# schematic.net
KiCad netlist of a schematic drawn in EAGLE
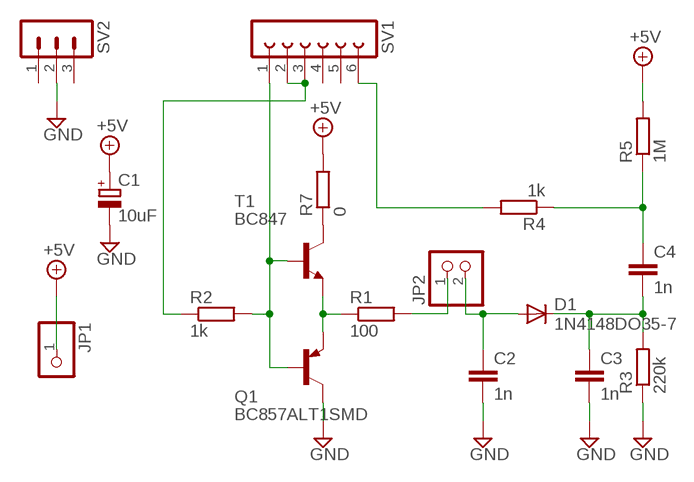
[diagram p0: schematic, sheet 1]

(export (version "E")
  (design (tool "Eeschema 10.0.6"))
  (components
    (comp (ref "C1")
      (value "10uF")
      (footprint "eagle-import:E2,5-6")
      (libsource (lib "eagle-import") (part "CPOL-EUE2.5-6"))
    )
    (comp (ref "C2")
      (value "1n")
      (footprint "eagle-import:C050-024X044")
      (libsource (lib "eagle-import") (part "C-EU050-024X044"))
    )
    (comp (ref "C3")
      (value "1n")
      (footprint "eagle-import:C050-024X044")
      (libsource (lib "eagle-import") (part "C-EU050-024X044"))
    )
    (comp (ref "C4")
      (value "1n")
      (footprint "eagle-import:C050-024X044")
      (libsource (lib "eagle-import") (part "C-EU050-024X044"))
    )
    (comp (ref "D1")
      (value "1N4148DO35-7")
      (footprint "eagle-import:DO35-7")
      (libsource (lib "eagle-import") (part "1N4148DO35-7"))
    )
    (comp (ref "JP1")
      (value "PINHD-1X1")
      (footprint "eagle-import:1X01")
      (libsource (lib "eagle-import") (part "PINHD-1X1"))
    )
    (comp (ref "JP2")
      (value "PINHD-1X2")
      (footprint "eagle-import:1X02")
      (libsource (lib "eagle-import") (part "PINHD-1X2"))
    )
    (comp (ref "Q1")
      (value "BC857ALT1SMD")
      (footprint "eagle-import:SOT23-BEC")
      (libsource (lib "eagle-import") (part "BC857SMDALT1"))
    )
    (comp (ref "R1")
      (value "100")
      (footprint "eagle-import:0207_10")
      (libsource (lib "eagle-import") (part "R-EU_0207/10"))
    )
    (comp (ref "R2")
      (value "1k")
      (footprint "eagle-import:0207_10")
      (libsource (lib "eagle-import") (part "R-EU_0207/10"))
    )
    (comp (ref "R3")
      (value "220k")
      (footprint "eagle-import:0207_10")
      (libsource (lib "eagle-import") (part "R-EU_0207/10"))
    )
    (comp (ref "R4")
      (value "1k")
      (footprint "eagle-import:0207_10")
      (libsource (lib "eagle-import") (part "R-EU_0207/10"))
    )
    (comp (ref "R5")
      (value "1M")
      (footprint "eagle-import:0207_10")
      (libsource (lib "eagle-import") (part "R-EU_0207/10"))
    )
    (comp (ref "R7")
      (value "0")
      (footprint "eagle-import:0204_5")
      (libsource (lib "eagle-import") (part "R-EU_0204/5"))
    )
    (comp (ref "SV1")
      (value "FE06-1")
      (footprint "eagle-import:FE06")
      (libsource (lib "eagle-import") (part "FE06-1"))
    )
    (comp (ref "SV2")
      (value "MA03-1")
      (footprint "eagle-import:MA03-1")
      (libsource (lib "eagle-import") (part "MA03-1"))
    )
    (comp (ref "T1")
      (value "BC847")
      (footprint "eagle-import:SOT23")
      (libsource (lib "eagle-import") (part "BC847"))
    )
  )
  (nets
    (net (code "1") (name "+5V") (class "Default")
      (node (ref "C1") (pin "+") (pinfunction "+_+") (pintype "passive"))
      (node (ref "JP1") (pin "1") (pinfunction "1_1") (pintype "passive"))
      (node (ref "R5") (pin "2") (pinfunction "2_2") (pintype "passive"))
      (node (ref "R7") (pin "2") (pinfunction "2_2") (pintype "passive"))
    )
    (net (code "2") (name "GND") (class "Default")
      (node (ref "C1") (pin "-") (pinfunction "-_-") (pintype "passive"))
      (node (ref "C2") (pin "2") (pinfunction "2_2") (pintype "passive"))
      (node (ref "C3") (pin "2") (pinfunction "2_2") (pintype "passive"))
      (node (ref "Q1") (pin "C") (pinfunction "C_C") (pintype "passive"))
      (node (ref "R3") (pin "1") (pinfunction "1_1") (pintype "passive"))
      (node (ref "SV2") (pin "2") (pinfunction "2_2") (pintype "passive"))
    )
    (net (code "3") (name "Net-(C2-Pad1)") (class "Default")
      (node (ref "C2") (pin "1") (pinfunction "1_1") (pintype "passive"))
      (node (ref "D1") (pin "A") (pinfunction "A_A") (pintype "passive"))
      (node (ref "JP2") (pin "2") (pinfunction "2_2") (pintype "passive"))
    )
    (net (code "4") (name "Net-(C3-Pad1)") (class "Default")
      (node (ref "C3") (pin "1") (pinfunction "1_1") (pintype "passive"))
      (node (ref "C4") (pin "2") (pinfunction "2_2") (pintype "passive"))
      (node (ref "D1") (pin "C") (pinfunction "C_C") (pintype "passive"))
      (node (ref "R3") (pin "2") (pinfunction "2_2") (pintype "passive"))
    )
    (net (code "5") (name "Net-(C4-Pad1)") (class "Default")
      (node (ref "C4") (pin "1") (pinfunction "1_1") (pintype "passive"))
      (node (ref "R4") (pin "1") (pinfunction "1_1") (pintype "passive"))
      (node (ref "R5") (pin "1") (pinfunction "1_1") (pintype "passive"))
    )
    (net (code "6") (name "Net-(JP2-Pad1)") (class "Default")
      (node (ref "JP2") (pin "1") (pinfunction "1_1") (pintype "passive"))
      (node (ref "R1") (pin "2") (pinfunction "2_2") (pintype "passive"))
    )
    (net (code "7") (name "Net-(R2-Pad1)") (class "Default")
      (node (ref "R2") (pin "1") (pinfunction "1_1") (pintype "passive"))
      (node (ref "SV1") (pin "2") (pinfunction "2_2") (pintype "passive"))
      (node (ref "SV1") (pin "3") (pinfunction "3_3") (pintype "passive"))
    )
    (net (code "8") (name "Net-(R4-Pad2)") (class "Default")
      (node (ref "R4") (pin "2") (pinfunction "2_2") (pintype "passive"))
      (node (ref "SV1") (pin "6") (pinfunction "6_6") (pintype "passive"))
    )
    (net (code "9") (name "Net-(T1-B)") (class "Default")
      (node (ref "Q1") (pin "B") (pinfunction "B_B") (pintype "passive"))
      (node (ref "R2") (pin "2") (pinfunction "2_2") (pintype "passive"))
      (node (ref "SV1") (pin "1") (pinfunction "1_1") (pintype "passive"))
      (node (ref "T1") (pin "1") (pinfunction "B_1") (pintype "passive"))
    )
    (net (code "10") (name "Net-(T1-C)") (class "Default")
      (node (ref "R7") (pin "1") (pinfunction "1_1") (pintype "passive"))
      (node (ref "T1") (pin "3") (pinfunction "C_3") (pintype "passive"))
    )
    (net (code "11") (name "Net-(T1-E)") (class "Default")
      (node (ref "Q1") (pin "E") (pinfunction "E_E") (pintype "passive"))
      (node (ref "R1") (pin "1") (pinfunction "1_1") (pintype "passive"))
      (node (ref "T1") (pin "2") (pinfunction "E_2") (pintype "passive"))
    )
    (net (code "12") (name "unconnected-(SV1-Pad4)") (class "Default")
      (node (ref "SV1") (pin "4") (pinfunction "4_4") (pintype "passive"))
    )
    (net (code "13") (name "unconnected-(SV1-Pad5)") (class "Default")
      (node (ref "SV1") (pin "5") (pinfunction "5_5") (pintype "passive"))
    )
    (net (code "14") (name "unconnected-(SV2-Pad1)") (class "Default")
      (node (ref "SV2") (pin "1") (pinfunction "1_1") (pintype "passive"))
    )
    (net (code "15") (name "unconnected-(SV2-Pad3)") (class "Default")
      (node (ref "SV2") (pin "3") (pinfunction "3_3") (pintype "passive"))
    )
  )
)
